# IMSAI_SIO_Emulation.net
KiCad netlist of a schematic drawn in Altium Designer
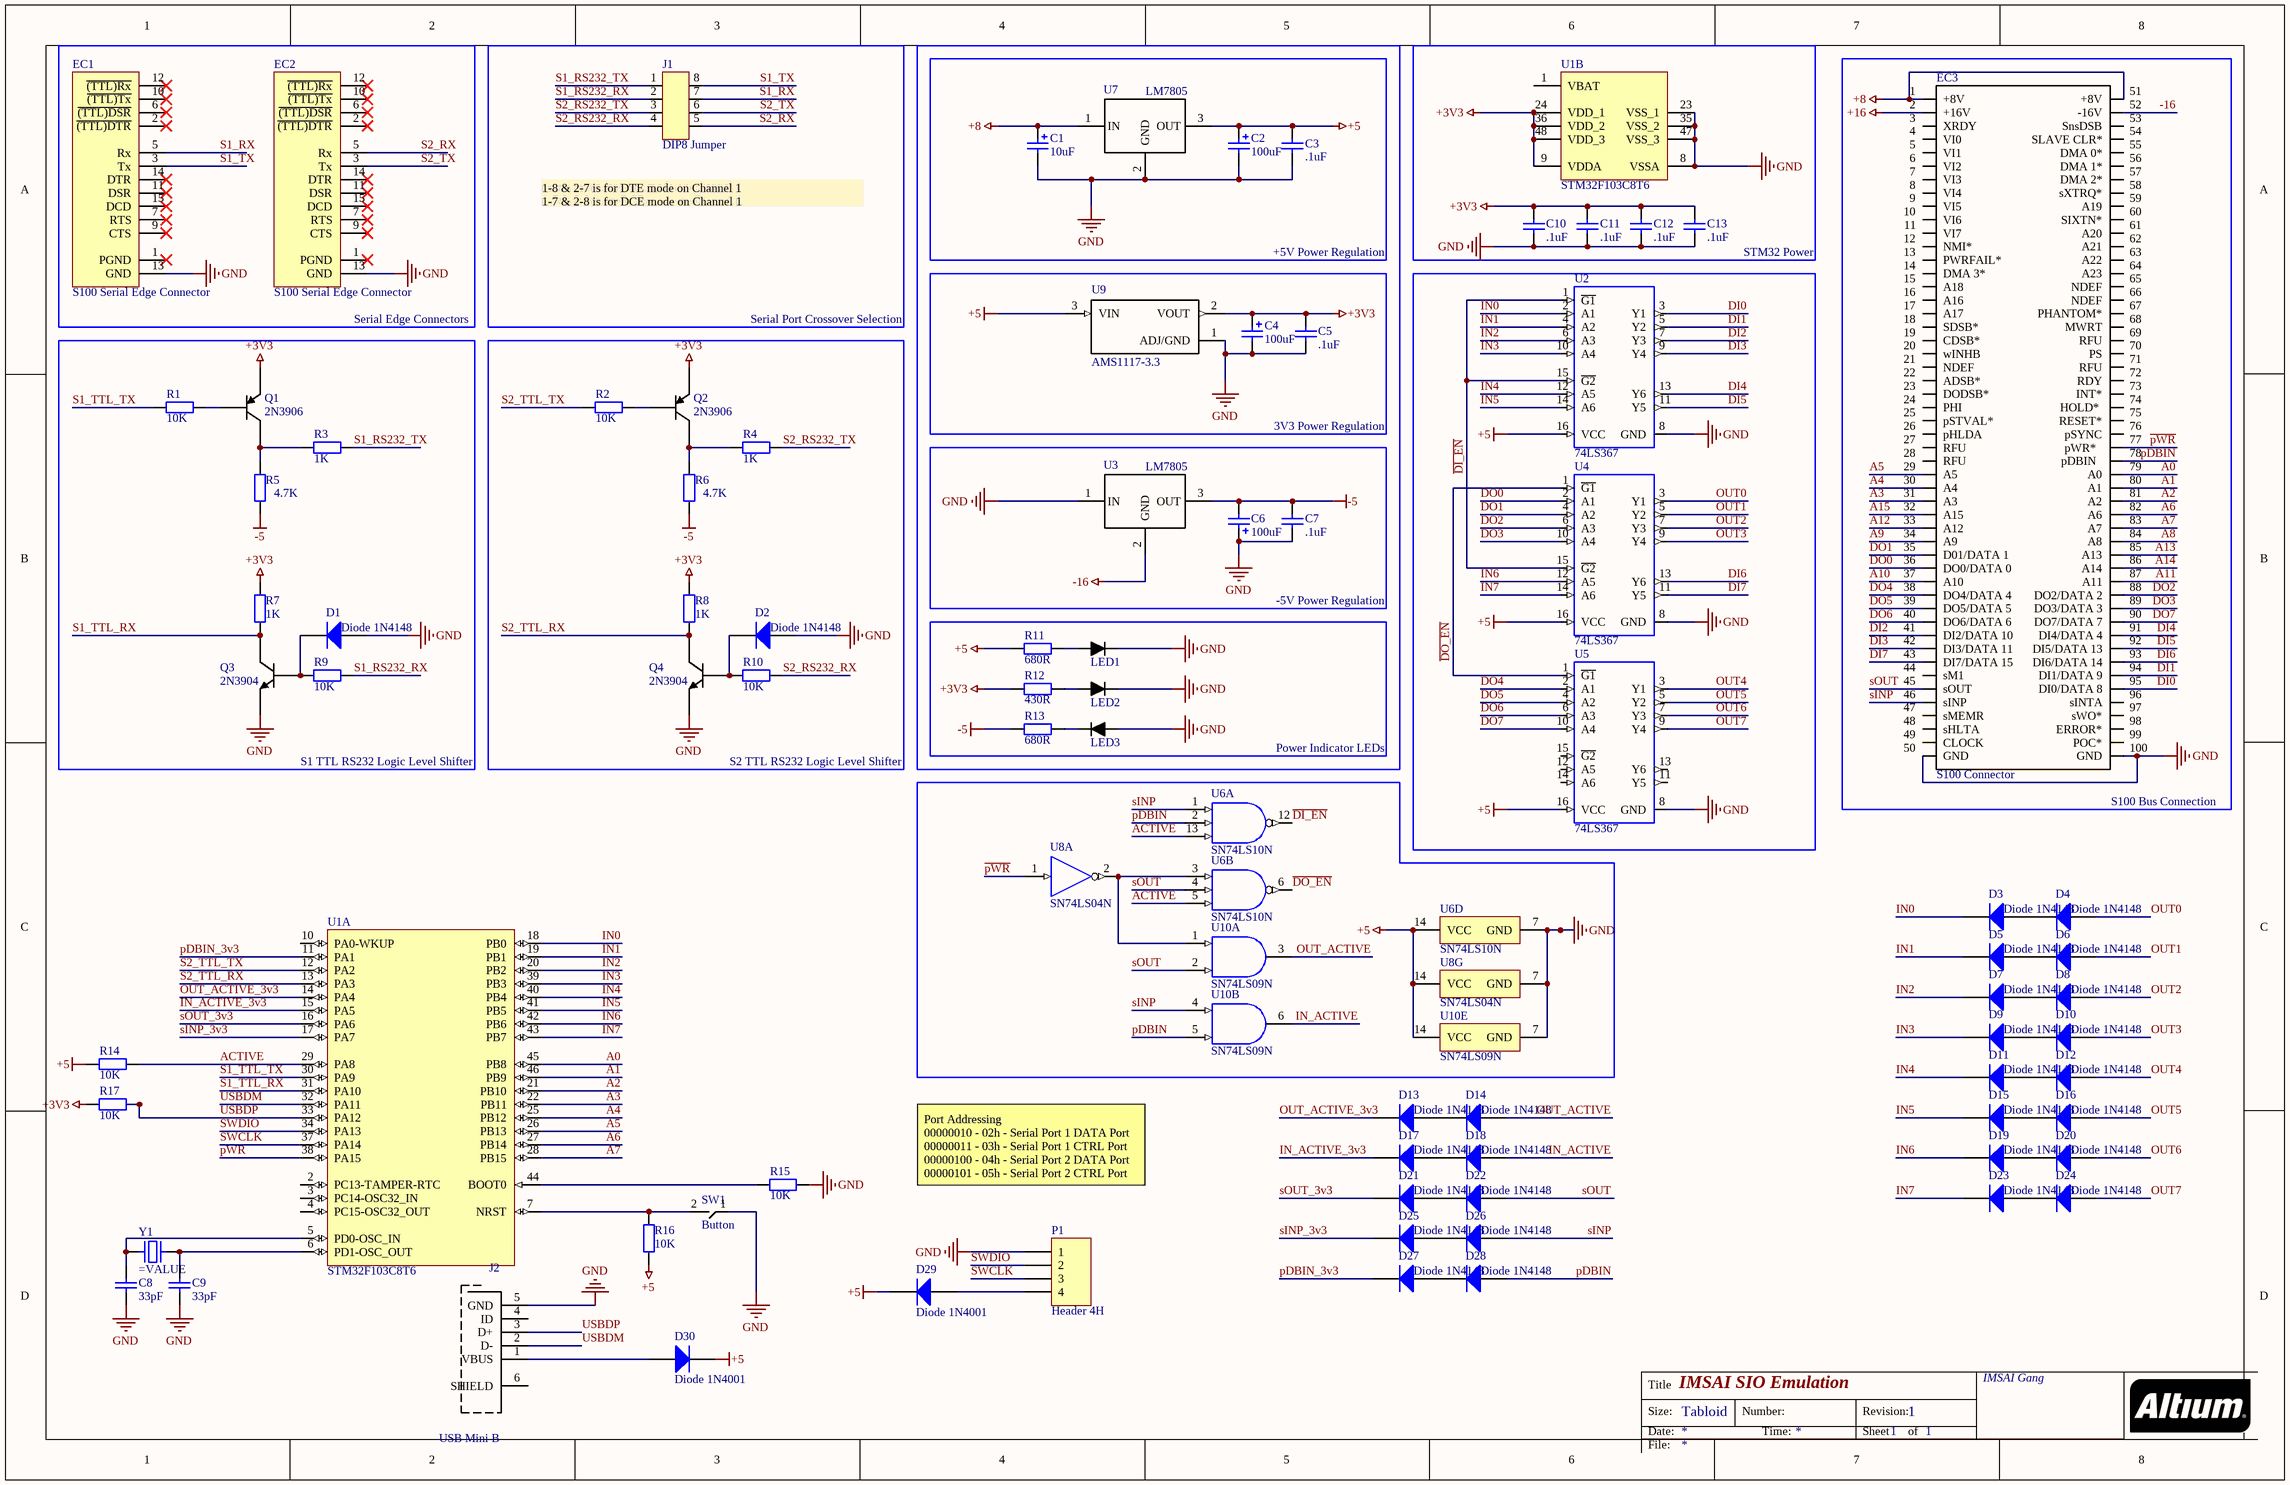
[diagram p0: IMSAI_SIO_Emulation.SchDoc]

(export (version "E")
  (design (tool "Eeschema 10.0.6"))
  (components
    (comp (ref "C1")
      (value "10uF")
      (footprint "Cap THT 2.5-5-11")
      (fields (field (name "Comment") "Capacitor 10uF") (field (name "PUBLISHER") "Altium Limited"))
      (libsource (lib "S100 SCHLIB") (part "Capacitor 10uF"))
    )
    (comp (ref "C2")
      (value "100uF")
      (footprint "CAP THT 2.5-6.5-12")
      (fields (field (name "Comment") "Capacitor 100uF") (field (name "PUBLISHER") "Altium Limited"))
      (libsource (lib "S100 SCHLIB") (part "Capacitor 100uF"))
    )
    (comp (ref "C3")
      (value ".1uF")
      (footprint "CAP THT 2.5x5x5")
      (fields (field (name "Comment") "Capacitor .1uF") (field (name "PUBLISHER") "Altium Limited"))
      (libsource (lib "S100 SCHLIB") (part "Capacitor .1uF"))
    )
    (comp (ref "C4")
      (value "100uF")
      (footprint "CAP THT 2.5-6.5-12")
      (fields (field (name "Comment") "Capacitor 100uF") (field (name "PUBLISHER") "Altium Limited"))
      (libsource (lib "S100 SCHLIB") (part "Capacitor 100uF"))
    )
    (comp (ref "C5")
      (value ".1uF")
      (footprint "CAP THT 2.5x5x5")
      (fields (field (name "Comment") "Capacitor .1uF") (field (name "PUBLISHER") "Altium Limited"))
      (libsource (lib "S100 SCHLIB") (part "Capacitor .1uF"))
    )
    (comp (ref "C6")
      (value "100uF")
      (footprint "CAP THT 2.5-6.5-12")
      (fields (field (name "Comment") "Capacitor 100uF") (field (name "PUBLISHER") "Altium Limited"))
      (libsource (lib "S100 SCHLIB") (part "Capacitor 100uF"))
    )
    (comp (ref "C7")
      (value ".1uF")
      (footprint "CAP THT 2.5x5x5")
      (fields (field (name "Comment") "Capacitor .1uF") (field (name "PUBLISHER") "Altium Limited"))
      (libsource (lib "S100 SCHLIB") (part "Capacitor .1uF"))
    )
    (comp (ref "C8")
      (value "33pF")
      (footprint "Cap THT 2.5-2-4 Ceramic")
      (fields (field (name "Comment") "Capacitor 33pF") (field (name "PUBLISHER") "Altium Limited"))
      (libsource (lib "S100 SCHLIB") (part "Capacitor 33pF"))
    )
    (comp (ref "C9")
      (value "33pF")
      (footprint "Cap THT 2.5-2-4 Ceramic")
      (fields (field (name "Comment") "Capacitor 33pF") (field (name "PUBLISHER") "Altium Limited"))
      (libsource (lib "S100 SCHLIB") (part "Capacitor 33pF"))
    )
    (comp (ref "C10")
      (value ".1uF")
      (footprint "CAP THT 2.5x5x5")
      (fields (field (name "Comment") "Capacitor .1uF") (field (name "PUBLISHER") "Altium Limited"))
      (libsource (lib "S100 SCHLIB") (part "Capacitor .1uF"))
    )
    (comp (ref "C11")
      (value ".1uF")
      (footprint "CAP THT 2.5x5x5")
      (fields (field (name "Comment") "Capacitor .1uF") (field (name "PUBLISHER") "Altium Limited"))
      (libsource (lib "S100 SCHLIB") (part "Capacitor .1uF"))
    )
    (comp (ref "C12")
      (value ".1uF")
      (footprint "CAP THT 2.5x5x5")
      (fields (field (name "Comment") "Capacitor .1uF") (field (name "PUBLISHER") "Altium Limited"))
      (libsource (lib "S100 SCHLIB") (part "Capacitor .1uF"))
    )
    (comp (ref "C13")
      (value ".1uF")
      (footprint "CAP THT 2.5x5x5")
      (fields (field (name "Comment") "Capacitor .1uF") (field (name "PUBLISHER") "Altium Limited"))
      (libsource (lib "S100 SCHLIB") (part "Capacitor .1uF"))
    )
    (comp (ref "D1")
      (value "Diode 1N4148")
      (footprint "DO-35")
      (description "High Conductance Fast Diode")
      (fields (field (name "PUBLISHER") "Altium Limited"))
      (libsource (lib "Miscellaneous Devices") (part "Diode 1N4148"))
    )
    (comp (ref "D2")
      (value "Diode 1N4148")
      (footprint "DO-35")
      (description "High Conductance Fast Diode")
      (fields (field (name "PUBLISHER") "Altium Limited"))
      (libsource (lib "Miscellaneous Devices") (part "Diode 1N4148"))
    )
    (comp (ref "D3")
      (value "Diode 1N4148")
      (footprint "DO-35")
      (description "High Conductance Fast Diode")
      (fields (field (name "PUBLISHER") "Altium Limited"))
      (libsource (lib "Miscellaneous Devices") (part "Diode 1N4148"))
    )
    (comp (ref "D4")
      (value "Diode 1N4148")
      (footprint "DO-35")
      (description "High Conductance Fast Diode")
      (fields (field (name "PUBLISHER") "Altium Limited"))
      (libsource (lib "Miscellaneous Devices") (part "Diode 1N4148"))
    )
    (comp (ref "D5")
      (value "Diode 1N4148")
      (footprint "DO-35")
      (description "High Conductance Fast Diode")
      (fields (field (name "PUBLISHER") "Altium Limited"))
      (libsource (lib "Miscellaneous Devices") (part "Diode 1N4148"))
    )
    (comp (ref "D6")
      (value "Diode 1N4148")
      (footprint "DO-35")
      (description "High Conductance Fast Diode")
      (fields (field (name "PUBLISHER") "Altium Limited"))
      (libsource (lib "Miscellaneous Devices") (part "Diode 1N4148"))
    )
    (comp (ref "D7")
      (value "Diode 1N4148")
      (footprint "DO-35")
      (description "High Conductance Fast Diode")
      (fields (field (name "PUBLISHER") "Altium Limited"))
      (libsource (lib "Miscellaneous Devices") (part "Diode 1N4148"))
    )
    (comp (ref "D8")
      (value "Diode 1N4148")
      (footprint "DO-35")
      (description "High Conductance Fast Diode")
      (fields (field (name "PUBLISHER") "Altium Limited"))
      (libsource (lib "Miscellaneous Devices") (part "Diode 1N4148"))
    )
    (comp (ref "D9")
      (value "Diode 1N4148")
      (footprint "DO-35")
      (description "High Conductance Fast Diode")
      (fields (field (name "PUBLISHER") "Altium Limited"))
      (libsource (lib "Miscellaneous Devices") (part "Diode 1N4148"))
    )
    (comp (ref "D10")
      (value "Diode 1N4148")
      (footprint "DO-35")
      (description "High Conductance Fast Diode")
      (fields (field (name "PUBLISHER") "Altium Limited"))
      (libsource (lib "Miscellaneous Devices") (part "Diode 1N4148"))
    )
    (comp (ref "D11")
      (value "Diode 1N4148")
      (footprint "DO-35")
      (description "High Conductance Fast Diode")
      (fields (field (name "PUBLISHER") "Altium Limited"))
      (libsource (lib "Miscellaneous Devices") (part "Diode 1N4148"))
    )
    (comp (ref "D12")
      (value "Diode 1N4148")
      (footprint "DO-35")
      (description "High Conductance Fast Diode")
      (fields (field (name "PUBLISHER") "Altium Limited"))
      (libsource (lib "Miscellaneous Devices") (part "Diode 1N4148"))
    )
    (comp (ref "D13")
      (value "Diode 1N4148")
      (footprint "DO-35")
      (description "High Conductance Fast Diode")
      (fields (field (name "PUBLISHER") "Altium Limited"))
      (libsource (lib "Miscellaneous Devices") (part "Diode 1N4148"))
    )
    (comp (ref "D14")
      (value "Diode 1N4148")
      (footprint "DO-35")
      (description "High Conductance Fast Diode")
      (fields (field (name "PUBLISHER") "Altium Limited"))
      (libsource (lib "Miscellaneous Devices") (part "Diode 1N4148"))
    )
    (comp (ref "D15")
      (value "Diode 1N4148")
      (footprint "DO-35")
      (description "High Conductance Fast Diode")
      (fields (field (name "PUBLISHER") "Altium Limited"))
      (libsource (lib "Miscellaneous Devices") (part "Diode 1N4148"))
    )
    (comp (ref "D16")
      (value "Diode 1N4148")
      (footprint "DO-35")
      (description "High Conductance Fast Diode")
      (fields (field (name "PUBLISHER") "Altium Limited"))
      (libsource (lib "Miscellaneous Devices") (part "Diode 1N4148"))
    )
    (comp (ref "D17")
      (value "Diode 1N4148")
      (footprint "DO-35")
      (description "High Conductance Fast Diode")
      (fields (field (name "PUBLISHER") "Altium Limited"))
      (libsource (lib "Miscellaneous Devices") (part "Diode 1N4148"))
    )
    (comp (ref "D18")
      (value "Diode 1N4148")
      (footprint "DO-35")
      (description "High Conductance Fast Diode")
      (fields (field (name "PUBLISHER") "Altium Limited"))
      (libsource (lib "Miscellaneous Devices") (part "Diode 1N4148"))
    )
    (comp (ref "D19")
      (value "Diode 1N4148")
      (footprint "DO-35")
      (description "High Conductance Fast Diode")
      (fields (field (name "PUBLISHER") "Altium Limited"))
      (libsource (lib "Miscellaneous Devices") (part "Diode 1N4148"))
    )
    (comp (ref "D20")
      (value "Diode 1N4148")
      (footprint "DO-35")
      (description "High Conductance Fast Diode")
      (fields (field (name "PUBLISHER") "Altium Limited"))
      (libsource (lib "Miscellaneous Devices") (part "Diode 1N4148"))
    )
    (comp (ref "D21")
      (value "Diode 1N4148")
      (footprint "DO-35")
      (description "High Conductance Fast Diode")
      (fields (field (name "PUBLISHER") "Altium Limited"))
      (libsource (lib "Miscellaneous Devices") (part "Diode 1N4148"))
    )
    (comp (ref "D22")
      (value "Diode 1N4148")
      (footprint "DO-35")
      (description "High Conductance Fast Diode")
      (fields (field (name "PUBLISHER") "Altium Limited"))
      (libsource (lib "Miscellaneous Devices") (part "Diode 1N4148"))
    )
    (comp (ref "D23")
      (value "Diode 1N4148")
      (footprint "DO-35")
      (description "High Conductance Fast Diode")
      (fields (field (name "PUBLISHER") "Altium Limited"))
      (libsource (lib "Miscellaneous Devices") (part "Diode 1N4148"))
    )
    (comp (ref "D24")
      (value "Diode 1N4148")
      (footprint "DO-35")
      (description "High Conductance Fast Diode")
      (fields (field (name "PUBLISHER") "Altium Limited"))
      (libsource (lib "Miscellaneous Devices") (part "Diode 1N4148"))
    )
    (comp (ref "D25")
      (value "Diode 1N4148")
      (footprint "DO-35")
      (description "High Conductance Fast Diode")
      (fields (field (name "PUBLISHER") "Altium Limited"))
      (libsource (lib "Miscellaneous Devices") (part "Diode 1N4148"))
    )
    (comp (ref "D26")
      (value "Diode 1N4148")
      (footprint "DO-35")
      (description "High Conductance Fast Diode")
      (fields (field (name "PUBLISHER") "Altium Limited"))
      (libsource (lib "Miscellaneous Devices") (part "Diode 1N4148"))
    )
    (comp (ref "D27")
      (value "Diode 1N4148")
      (footprint "DO-35")
      (description "High Conductance Fast Diode")
      (fields (field (name "PUBLISHER") "Altium Limited"))
      (libsource (lib "Miscellaneous Devices") (part "Diode 1N4148"))
    )
    (comp (ref "D28")
      (value "Diode 1N4148")
      (footprint "DO-35")
      (description "High Conductance Fast Diode")
      (fields (field (name "PUBLISHER") "Altium Limited"))
      (libsource (lib "Miscellaneous Devices") (part "Diode 1N4148"))
    )
    (comp (ref "D29")
      (value "Diode 1N4001")
      (footprint "DO-41")
      (description "1 Amp General Purpose Rectifier")
      (fields (field (name "PUBLISHER") "Altium Limited"))
      (libsource (lib "Miscellaneous Devices") (part "Diode 1N4001"))
    )
    (comp (ref "D30")
      (value "Diode 1N4001")
      (footprint "DO-41")
      (description "1 Amp General Purpose Rectifier")
      (fields (field (name "PUBLISHER") "Altium Limited"))
      (libsource (lib "Miscellaneous Devices") (part "Diode 1N4001"))
    )
    (comp (ref "EC1")
      (value "S100 Serial Edge Connector")
      (footprint "E26 Edge Connector")
      (libsource (lib "S100 SCHLIB") (part "S100 Serial Edge Connector"))
    )
    (comp (ref "EC2")
      (value "S100 Serial Edge Connector")
      (footprint "E26 Edge Connector")
      (libsource (lib "S100 SCHLIB") (part "S100 Serial Edge Connector"))
    )
    (comp (ref "EC3")
      (value "S100 Connector")
      (footprint "S100")
      (libsource (lib "S100 SCHLIB") (part "S100 Connector"))
    )
    (comp (ref "J1")
      (value "DIP8 Jumper")
      (footprint "DIP8")
      (libsource (lib "S100 SCHLIB") (part "DIP8 Jumper"))
    )
    (comp (ref "J2")
      (value "USB Mini B")
      (footprint "USB Mini B")
      (description "MINI USB A - 5POS Horizontal through hole")
      (fields (field (name "MF") "Wurth Electronics") (field (name "MP") "651005136521"))
      (libsource (lib "S100 SCHLIB") (part "USB Mini B"))
    )
    (comp (ref "LED1")
      (value "Generic LED 5mm")
      (footprint "LED 5mm THT")
      (libsource (lib "S100 SCHLIB") (part "Generic LED 5mm"))
    )
    (comp (ref "LED2")
      (value "Generic LED 5mm")
      (footprint "LED 5mm THT")
      (libsource (lib "S100 SCHLIB") (part "Generic LED 5mm"))
    )
    (comp (ref "LED3")
      (value "Generic LED 5mm")
      (footprint "LED 5mm THT")
      (libsource (lib "S100 SCHLIB") (part "Generic LED 5mm"))
    )
    (comp (ref "P1")
      (value "Header 4H")
      (footprint "HDR1X4H")
      (description "Header, 4-Pin, Right Angle")
      (fields (field (name "PUBLISHER") "Altium Limited"))
      (libsource (lib "Miscellaneous Connectors") (part "Header 4H"))
    )
    (comp (ref "Q1")
      (value "2N3906")
      (footprint "TO-92A")
      (description "2N3906 GP PNP")
      (fields (field (name "PUBLISHER") "Altium Limited"))
      (libsource (lib "S100 SCHLIB") (part "2N3906"))
    )
    (comp (ref "Q2")
      (value "2N3906")
      (footprint "TO-92A")
      (description "2N3906 GP PNP")
      (fields (field (name "PUBLISHER") "Altium Limited"))
      (libsource (lib "S100 SCHLIB") (part "2N3906"))
    )
    (comp (ref "Q3")
      (value "2N3904")
      (footprint "TO-92A")
      (description "NPN General Purpose Amplifier")
      (fields (field (name "PUBLISHER") "Altium Limited"))
      (libsource (lib "S100 SCHLIB") (part "2N3904"))
    )
    (comp (ref "Q4")
      (value "2N3904")
      (footprint "TO-92A")
      (description "NPN General Purpose Amplifier")
      (fields (field (name "PUBLISHER") "Altium Limited"))
      (libsource (lib "S100 SCHLIB") (part "2N3904"))
    )
    (comp (ref "R1")
      (value "Res2")
      (footprint "AXIAL-0.4")
      (description "Resistor")
      (fields (field (name "ALTIUM_UNNAMED_1") "10K") (field (name "PUBLISHER") "Altium Limited"))
      (libsource (lib "Miscellaneous Devices") (part "Res2"))
    )
    (comp (ref "R2")
      (value "Res2")
      (footprint "AXIAL-0.4")
      (description "Resistor")
      (fields (field (name "ALTIUM_UNNAMED_1") "10K") (field (name "PUBLISHER") "Altium Limited"))
      (libsource (lib "Miscellaneous Devices") (part "Res2"))
    )
    (comp (ref "R3")
      (value "Res2")
      (footprint "AXIAL-0.4")
      (description "Resistor")
      (fields (field (name "ALTIUM_UNNAMED_1") "1K") (field (name "PUBLISHER") "Altium Limited"))
      (libsource (lib "Miscellaneous Devices") (part "Res2"))
    )
    (comp (ref "R4")
      (value "Res2")
      (footprint "AXIAL-0.4")
      (description "Resistor")
      (fields (field (name "ALTIUM_UNNAMED_1") "1K") (field (name "PUBLISHER") "Altium Limited"))
      (libsource (lib "Miscellaneous Devices") (part "Res2"))
    )
    (comp (ref "R5")
      (value "Res2")
      (footprint "AXIAL-0.4")
      (description "Resistor")
      (fields (field (name "ALTIUM_UNNAMED_1") "4.7K") (field (name "PUBLISHER") "Altium Limited"))
      (libsource (lib "") (part "Res2_2"))
    )
    (comp (ref "R6")
      (value "Res2")
      (footprint "AXIAL-0.4")
      (description "Resistor")
      (fields (field (name "ALTIUM_UNNAMED_1") "4.7K") (field (name "PUBLISHER") "Altium Limited"))
      (libsource (lib "") (part "Res2_2"))
    )
    (comp (ref "R7")
      (value "Res2")
      (footprint "AXIAL-0.4")
      (description "Resistor")
      (fields (field (name "ALTIUM_UNNAMED_1") "1K") (field (name "PUBLISHER") "Altium Limited"))
      (libsource (lib "") (part "Res2_1"))
    )
    (comp (ref "R8")
      (value "Res2")
      (footprint "AXIAL-0.4")
      (description "Resistor")
      (fields (field (name "ALTIUM_UNNAMED_1") "1K") (field (name "PUBLISHER") "Altium Limited"))
      (libsource (lib "") (part "Res2_1"))
    )
    (comp (ref "R9")
      (value "Res2")
      (footprint "AXIAL-0.4")
      (description "Resistor")
      (fields (field (name "ALTIUM_UNNAMED_1") "10K") (field (name "PUBLISHER") "Altium Limited"))
      (libsource (lib "Miscellaneous Devices") (part "Res2"))
    )
    (comp (ref "R10")
      (value "Res2")
      (footprint "AXIAL-0.4")
      (description "Resistor")
      (fields (field (name "ALTIUM_UNNAMED_1") "10K") (field (name "PUBLISHER") "Altium Limited"))
      (libsource (lib "Miscellaneous Devices") (part "Res2"))
    )
    (comp (ref "R11")
      (value "Res2")
      (footprint "AXIAL-0.4")
      (description "Resistor")
      (fields (field (name "ALTIUM_UNNAMED_1") "680R") (field (name "PUBLISHER") "Altium Limited"))
      (libsource (lib "Miscellaneous Devices") (part "Res2"))
    )
    (comp (ref "R12")
      (value "Res2")
      (footprint "AXIAL-0.4")
      (description "Resistor")
      (fields (field (name "ALTIUM_UNNAMED_1") "430R") (field (name "PUBLISHER") "Altium Limited"))
      (libsource (lib "Miscellaneous Devices") (part "Res2"))
    )
    (comp (ref "R13")
      (value "Res2")
      (footprint "AXIAL-0.4")
      (description "Resistor")
      (fields (field (name "ALTIUM_UNNAMED_1") "680R") (field (name "PUBLISHER") "Altium Limited"))
      (libsource (lib "Miscellaneous Devices") (part "Res2"))
    )
    (comp (ref "R14")
      (value "Res2")
      (footprint "AXIAL-0.4")
      (description "Resistor")
      (fields (field (name "ALTIUM_UNNAMED_1") "10K") (field (name "PUBLISHER") "Altium Limited"))
      (libsource (lib "Miscellaneous Devices") (part "Res2"))
    )
    (comp (ref "R15")
      (value "Res2")
      (footprint "AXIAL-0.4")
      (description "Resistor")
      (fields (field (name "ALTIUM_UNNAMED_1") "10K") (field (name "PUBLISHER") "Altium Limited"))
      (libsource (lib "Miscellaneous Devices") (part "Res2"))
    )
    (comp (ref "R16")
      (value "Res2")
      (footprint "AXIAL-0.4")
      (description "Resistor")
      (fields (field (name "ALTIUM_UNNAMED_1") "10K") (field (name "PUBLISHER") "Altium Limited"))
      (libsource (lib "") (part "Res2_1"))
    )
    (comp (ref "R17")
      (value "Res2")
      (footprint "AXIAL-0.4")
      (description "Resistor")
      (fields (field (name "ALTIUM_UNNAMED_1") "10K") (field (name "PUBLISHER") "Altium Limited"))
      (libsource (lib "Miscellaneous Devices") (part "Res2"))
    )
    (comp (ref "SW1")
      (value "Button")
      (footprint "SMD_PUSHBUTTON_LCSC")
      (description "LCSC Push button SMD")
      (libsource (lib "S100 SCHLIB") (part "Button"))
    )
    (comp (ref "U1")
      (value "STM32F103C8T6")
      (footprint "STM-LQFP48_L")
      (libsource (lib "STMicroelectronics STM32 F1") (part "STM32F103C8T6"))
    )
    (comp (ref "U2") (value "74LS367") (footprint "DIP16") (libsource (lib "S100 SCHLIB") (part "74LS367")))
    (comp (ref "U3")
      (value "LM7805")
      (footprint "TO220")
      (description "LM7805 Linear Voltage Regulator")
      (libsource (lib "S100 SCHLIB") (part "LM7805"))
    )
    (comp (ref "U4") (value "74LS367") (footprint "DIP16") (libsource (lib "S100 SCHLIB") (part "74LS367")))
    (comp (ref "U5") (value "74LS367") (footprint "DIP16") (libsource (lib "S100 SCHLIB") (part "74LS367")))
    (comp (ref "U6")
      (value "SN74LS10N")
      (footprint "N0014A")
      (description "Triple 3-input positive-NAND gates, N0014A, TUBE")
      (fields
        (field (name "GENERIC PART NUMBER") "SN74LS10")
        (field (name "MANUFACTURER") "Texas Instruments")
      )
      (libsource (lib "TI_Logic_Gate") (part "SN74LS10N"))
    )
    (comp (ref "U7")
      (value "LM7805")
      (footprint "TO220")
      (description "LM7805 Linear Voltage Regulator")
      (libsource (lib "S100 SCHLIB") (part "LM7805"))
    )
    (comp (ref "U8")
      (value "SN74LS04N")
      (footprint "N0014A")
      (description "Hex inverters, N0014A, TUBE")
      (fields
        (field (name "GENERIC PART NUMBER") "SN74LS04")
        (field (name "MANUFACTURER") "Texas Instruments")
      )
      (libsource (lib "TI_Logic_Buffer,Driver,Transceiver") (part "SN74LS04N"))
    )
    (comp (ref "U9")
      (value "AMS1117-3.3")
      (footprint "TO220")
      (description "1-Amp 3.3-Volt Low Drop Out Voltage Regulatator")
      (fields (field (name "MF") "Advanced Monolithic Systems"))
      (libsource (lib "S100 SCHLIB") (part "AMS1117-3.3"))
    )
    (comp (ref "U10")
      (value "SN74LS09N")
      (footprint "N0014A")
      (description "Quad 2-input positive-AND gates with open collector outputs, N0014A, TUBE")
      (fields
        (field (name "GENERIC PART NUMBER") "SN74LS09")
        (field (name "MANUFACTURER") "Texas Instruments")
      )
      (libsource (lib "TI_Logic_Gate") (part "SN74LS09N"))
    )
    (comp (ref "Y1")
      (value "~")
      (footprint "ABRACON ABLS")
      (description "SMT Crystal")
      (libsource (lib "S100 SCHLIB") (part "Abracon Crystal ABLS"))
    )
  )
  (nets
    (net (code "1") (name "+3V3") (class "Default")
      (node (ref "C10") (pin "2") (pinfunction "2_2") (pintype "passive"))
      (node (ref "C11") (pin "2") (pinfunction "2_2") (pintype "passive"))
      (node (ref "C12") (pin "2") (pinfunction "2_2") (pintype "passive"))
      (node (ref "C13") (pin "2") (pinfunction "2_2") (pintype "passive"))
      (node (ref "C4") (pin "1") (pinfunction "1_1") (pintype "passive"))
      (node (ref "C5") (pin "2") (pinfunction "2_2") (pintype "passive"))
      (node (ref "Q1") (pin "1") (pinfunction "E_1") (pintype "passive"))
      (node (ref "Q2") (pin "1") (pinfunction "E_1") (pintype "passive"))
      (node (ref "R12") (pin "2") (pinfunction "2_2") (pintype "passive"))
      (node (ref "R17") (pin "2") (pinfunction "2_2") (pintype "passive"))
      (node (ref "R7") (pin "1") (pinfunction "1_1") (pintype "passive"))
      (node (ref "R8") (pin "1") (pinfunction "1_1") (pintype "passive"))
      (node (ref "U1") (pin "24") (pinfunction "VDD_1_24") (pintype "power_in"))
      (node (ref "U1") (pin "36") (pinfunction "VDD_2_36") (pintype "power_in"))
      (node (ref "U1") (pin "48") (pinfunction "VDD_3_48") (pintype "power_in"))
      (node (ref "U1") (pin "9") (pinfunction "VDDA_9") (pintype "power_in"))
      (node (ref "U9") (pin "2") (pinfunction "VOUT_2") (pintype "output"))
    )
    (net (code "2") (name "+5") (class "Default")
      (node (ref "C2") (pin "1") (pinfunction "1_1") (pintype "passive"))
      (node (ref "C3") (pin "2") (pinfunction "2_2") (pintype "passive"))
      (node (ref "D29") (pin "2") (pinfunction "K_2") (pintype "passive"))
      (node (ref "D30") (pin "2") (pinfunction "K_2") (pintype "passive"))
      (node (ref "R11") (pin "2") (pinfunction "2_2") (pintype "passive"))
      (node (ref "R14") (pin "2") (pinfunction "2_2") (pintype "passive"))
      (node (ref "R16") (pin "2") (pinfunction "2_2") (pintype "passive"))
      (node (ref "U10") (pin "14") (pinfunction "VCC_14") (pintype "power_in"))
      (node (ref "U2") (pin "16") (pinfunction "VCC_16") (pintype "input"))
      (node (ref "U4") (pin "16") (pinfunction "VCC_16") (pintype "input"))
      (node (ref "U5") (pin "16") (pinfunction "VCC_16") (pintype "input"))
      (node (ref "U6") (pin "14") (pinfunction "VCC_14") (pintype "power_in"))
      (node (ref "U7") (pin "3") (pinfunction "OUT_3") (pintype "passive"))
      (node (ref "U8") (pin "14") (pinfunction "VCC_14") (pintype "power_in"))
      (node (ref "U9") (pin "3") (pinfunction "VIN_3") (pintype "input"))
    )
    (net (code "3") (name "+8") (class "Default")
      (node (ref "C1") (pin "1") (pinfunction "1_1") (pintype "passive"))
      (node (ref "EC3") (pin "1") (pinfunction "+8V_1") (pintype "passive"))
      (node (ref "EC3") (pin "51") (pinfunction "+8V_51") (pintype "passive"))
      (node (ref "U7") (pin "1") (pinfunction "IN_1") (pintype "passive"))
    )
    (net (code "4") (name "+16") (class "Default")
      (node (ref "EC3") (pin "2") (pinfunction "+16V_2") (pintype "passive"))
    )
    (net (code "5") (name "-5") (class "Default")
      (node (ref "C6") (pin "2") (pinfunction "2_2") (pintype "passive"))
      (node (ref "C7") (pin "1") (pinfunction "1_1") (pintype "passive"))
      (node (ref "R13") (pin "2") (pinfunction "2_2") (pintype "passive"))
      (node (ref "R5") (pin "1") (pinfunction "1_1") (pintype "passive"))
      (node (ref "R6") (pin "1") (pinfunction "1_1") (pintype "passive"))
      (node (ref "U3") (pin "3") (pinfunction "OUT_3") (pintype "passive"))
    )
    (net (code "6") (name "-16") (class "Default")
      (node (ref "EC3") (pin "52") (pinfunction "-16V_52") (pintype "passive"))
      (node (ref "U3") (pin "2") (pinfunction "GND_2") (pintype "passive"))
    )
    (net (code "7") (name "/A0") (class "Default")
      (node (ref "EC3") (pin "79") (pinfunction "A0_79") (pintype "passive"))
      (node (ref "U1") (pin "45") (pinfunction "PB8_45") (pintype "bidirectional"))
    )
    (net (code "8") (name "/A1") (class "Default")
      (node (ref "EC3") (pin "80") (pinfunction "A1_80") (pintype "passive"))
      (node (ref "U1") (pin "46") (pinfunction "PB9_46") (pintype "bidirectional"))
    )
    (net (code "9") (name "/A2") (class "Default")
      (node (ref "EC3") (pin "81") (pinfunction "A2_81") (pintype "passive"))
      (node (ref "U1") (pin "21") (pinfunction "PB10_21") (pintype "bidirectional"))
    )
    (net (code "10") (name "/A3") (class "Default")
      (node (ref "EC3") (pin "31") (pinfunction "A3_31") (pintype "passive"))
      (node (ref "U1") (pin "22") (pinfunction "PB11_22") (pintype "bidirectional"))
    )
    (net (code "11") (name "/A4") (class "Default")
      (node (ref "EC3") (pin "30") (pinfunction "A4_30") (pintype "passive"))
      (node (ref "U1") (pin "25") (pinfunction "PB12_25") (pintype "bidirectional"))
    )
    (net (code "12") (name "/A5") (class "Default")
      (node (ref "EC3") (pin "29") (pinfunction "A5_29") (pintype "passive"))
      (node (ref "U1") (pin "26") (pinfunction "PB13_26") (pintype "bidirectional"))
    )
    (net (code "13") (name "/A6") (class "Default")
      (node (ref "EC3") (pin "82") (pinfunction "A6_82") (pintype "passive"))
      (node (ref "U1") (pin "27") (pinfunction "PB14_27") (pintype "bidirectional"))
    )
    (net (code "14") (name "/A7") (class "Default")
      (node (ref "EC3") (pin "83") (pinfunction "A7_83") (pintype "passive"))
      (node (ref "U1") (pin "28") (pinfunction "PB15_28") (pintype "bidirectional"))
    )
    (net (code "15") (name "/A8") (class "Default")
      (node (ref "EC3") (pin "84") (pinfunction "A8_84") (pintype "passive"))
    )
    (net (code "16") (name "/A9") (class "Default")
      (node (ref "EC3") (pin "34") (pinfunction "A9_34") (pintype "passive"))
    )
    (net (code "17") (name "/A10") (class "Default")
      (node (ref "EC3") (pin "37") (pinfunction "A10_37") (pintype "passive"))
    )
    (net (code "18") (name "/A11") (class "Default")
      (node (ref "EC3") (pin "87") (pinfunction "A11_87") (pintype "passive"))
    )
    (net (code "19") (name "/A12") (class "Default")
      (node (ref "EC3") (pin "33") (pinfunction "A12_33") (pintype "passive"))
    )
    (net (code "20") (name "/A13") (class "Default")
      (node (ref "EC3") (pin "85") (pinfunction "A13_85") (pintype "passive"))
    )
    (net (code "21") (name "/A14") (class "Default")
      (node (ref "EC3") (pin "86") (pinfunction "A14_86") (pintype "passive"))
    )
    (net (code "22") (name "/A15") (class "Default")
      (node (ref "EC3") (pin "32") (pinfunction "A15_32") (pintype "passive"))
    )
    (net (code "23") (name "/ACTIVE") (class "Default")
      (node (ref "R14") (pin "1") (pinfunction "1_1") (pintype "passive"))
      (node (ref "U1") (pin "29") (pinfunction "PA8_29") (pintype "bidirectional"))
      (node (ref "U6") (pin "13") (pinfunction "1C_13") (pintype "input"))
      (node (ref "U6") (pin "5") (pinfunction "2C_5") (pintype "input"))
    )
    (net (code "24") (name "/DI0") (class "Default")
      (node (ref "EC3") (pin "95") (pinfunction "DI0/DATA_8_95") (pintype "passive"))
      (node (ref "U2") (pin "3") (pinfunction "Y1_3") (pintype "output"))
    )
    (net (code "25") (name "/DI1") (class "Default")
      (node (ref "EC3") (pin "94") (pinfunction "DI1/DATA_9_94") (pintype "passive"))
      (node (ref "U2") (pin "5") (pinfunction "Y2_5") (pintype "output"))
    )
    (net (code "26") (name "/DI2") (class "Default")
      (node (ref "EC3") (pin "41") (pinfunction "DI2/DATA_10_41") (pintype "passive"))
      (node (ref "U2") (pin "7") (pinfunction "Y3_7") (pintype "output"))
    )
    (net (code "27") (name "/DI3") (class "Default")
      (node (ref "EC3") (pin "42") (pinfunction "DI3/DATA_11_42") (pintype "passive"))
      (node (ref "U2") (pin "9") (pinfunction "Y4_9") (pintype "output"))
    )
    (net (code "28") (name "/DI4") (class "Default")
      (node (ref "EC3") (pin "91") (pinfunction "DI4/DATA_4_91") (pintype "passive"))
      (node (ref "U2") (pin "13") (pinfunction "Y6_13") (pintype "output"))
    )
    (net (code "29") (name "/DI5") (class "Default")
      (node (ref "EC3") (pin "92") (pinfunction "DI5/DATA_13_92") (pintype "passive"))
      (node (ref "U2") (pin "11") (pinfunction "Y5_11") (pintype "output"))
    )
    (net (code "30") (name "/DI6") (class "Default")
      (node (ref "EC3") (pin "93") (pinfunction "DI6/DATA_14_93") (pintype "passive"))
      (node (ref "U4") (pin "13") (pinfunction "Y6_13") (pintype "output"))
    )
    (net (code "31") (name "/DI7") (class "Default")
      (node (ref "EC3") (pin "43") (pinfunction "DI7/DATA_15_43") (pintype "passive"))
      (node (ref "U4") (pin "11") (pinfunction "Y5_11") (pintype "output"))
    )
    (net (code "32") (name "/DI_EN") (class "Default")
      (node (ref "U2") (pin "1") (pinfunction "G1_1") (pintype "input"))
      (node (ref "U2") (pin "15") (pinfunction "G2_15") (pintype "input"))
      (node (ref "U4") (pin "15") (pinfunction "G2_15") (pintype "input"))
      (node (ref "U6") (pin "12") (pinfunction "1Y_12") (pintype "output"))
    )
    (net (code "33") (name "/DO0") (class "Default")
      (node (ref "EC3") (pin "36") (pinfunction "DO0/DATA_0_36") (pintype "passive"))
      (node (ref "U4") (pin "2") (pinfunction "A1_2") (pintype "input"))
    )
    (net (code "34") (name "/DO1") (class "Default")
      (node (ref "EC3") (pin "35") (pinfunction "D01/DATA_1_35") (pintype "passive"))
      (node (ref "U4") (pin "4") (pinfunction "A2_4") (pintype "input"))
    )
    (net (code "35") (name "/DO2") (class "Default")
      (node (ref "EC3") (pin "88") (pinfunction "DO2/DATA_2_88") (pintype "passive"))
      (node (ref "U4") (pin "6") (pinfunction "A3_6") (pintype "input"))
    )
    (net (code "36") (name "/DO3") (class "Default")
      (node (ref "EC3") (pin "89") (pinfunction "DO3/DATA_3_89") (pintype "passive"))
      (node (ref "U4") (pin "10") (pinfunction "A4_10") (pintype "input"))
    )
    (net (code "37") (name "/DO4") (class "Default")
      (node (ref "EC3") (pin "38") (pinfunction "DO4/DATA_4_38") (pintype "passive"))
      (node (ref "U5") (pin "2") (pinfunction "A1_2") (pintype "input"))
    )
    (net (code "38") (name "/DO5") (class "Default")
      (node (ref "EC3") (pin "39") (pinfunction "DO5/DATA_5_39") (pintype "passive"))
      (node (ref "U5") (pin "4") (pinfunction "A2_4") (pintype "input"))
    )
    (net (code "39") (name "/DO6") (class "Default")
      (node (ref "EC3") (pin "40") (pinfunction "DO6/DATA_6_40") (pintype "passive"))
      (node (ref "U5") (pin "6") (pinfunction "A3_6") (pintype "input"))
    )
    (net (code "40") (name "/DO7") (class "Default")
      (node (ref "EC3") (pin "90") (pinfunction "DO7/DATA_7_90") (pintype "passive"))
      (node (ref "U5") (pin "10") (pinfunction "A4_10") (pintype "input"))
    )
    (net (code "41") (name "/DO_EN") (class "Default")
      (node (ref "U4") (pin "1") (pinfunction "G1_1") (pintype "input"))
      (node (ref "U5") (pin "1") (pinfunction "G1_1") (pintype "input"))
      (node (ref "U6") (pin "6") (pinfunction "2Y_6") (pintype "output"))
    )
    (net (code "42") (name "/IN0") (class "Default")
      (node (ref "D3") (pin "2") (pinfunction "K_2") (pintype "passive"))
      (node (ref "U1") (pin "18") (pinfunction "PB0_18") (pintype "bidirectional"))
      (node (ref "U2") (pin "2") (pinfunction "A1_2") (pintype "input"))
    )
    (net (code "43") (name "/IN1") (class "Default")
      (node (ref "D5") (pin "2") (pinfunction "K_2") (pintype "passive"))
      (node (ref "U1") (pin "19") (pinfunction "PB1_19") (pintype "bidirectional"))
      (node (ref "U2") (pin "4") (pinfunction "A2_4") (pintype "input"))
    )
    (net (code "44") (name "/IN2") (class "Default")
      (node (ref "D7") (pin "2") (pinfunction "K_2") (pintype "passive"))
      (node (ref "U1") (pin "20") (pinfunction "PB2_20") (pintype "bidirectional"))
      (node (ref "U2") (pin "6") (pinfunction "A3_6") (pintype "input"))
    )
    (net (code "45") (name "/IN3") (class "Default")
      (node (ref "D9") (pin "2") (pinfunction "K_2") (pintype "passive"))
      (node (ref "U1") (pin "39") (pinfunction "PB3_39") (pintype "bidirectional"))
      (node (ref "U2") (pin "10") (pinfunction "A4_10") (pintype "input"))
    )
    (net (code "46") (name "/IN4") (class "Default")
      (node (ref "D11") (pin "2") (pinfunction "K_2") (pintype "passive"))
      (node (ref "U1") (pin "40") (pinfunction "PB4_40") (pintype "bidirectional"))
      (node (ref "U2") (pin "12") (pinfunction "A5_12") (pintype "input"))
    )
    (net (code "47") (name "/IN5") (class "Default")
      (node (ref "D15") (pin "2") (pinfunction "K_2") (pintype "passive"))
      (node (ref "U1") (pin "41") (pinfunction "PB5_41") (pintype "bidirectional"))
      (node (ref "U2") (pin "14") (pinfunction "A6_14") (pintype "input"))
    )
    (net (code "48") (name "/IN6") (class "Default")
      (node (ref "D19") (pin "2") (pinfunction "K_2") (pintype "passive"))
      (node (ref "U1") (pin "42") (pinfunction "PB6_42") (pintype "bidirectional"))
      (node (ref "U4") (pin "12") (pinfunction "A5_12") (pintype "input"))
    )
    (net (code "49") (name "/IN7") (class "Default")
      (node (ref "D23") (pin "2") (pinfunction "K_2") (pintype "passive"))
      (node (ref "U1") (pin "43") (pinfunction "PB7_43") (pintype "bidirectional"))
      (node (ref "U4") (pin "14") (pinfunction "A6_14") (pintype "input"))
    )
    (net (code "50") (name "/IN_ACTIVE") (class "Default")
      (node (ref "D18") (pin "1") (pinfunction "A_1") (pintype "passive"))
      (node (ref "U10") (pin "6") (pinfunction "2Y_6") (pintype "open_collector"))
    )
    (net (code "51") (name "/IN_ACTIVE_3v3") (class "Default")
      (node (ref "D17") (pin "2") (pinfunction "K_2") (pintype "passive"))
      (node (ref "U1") (pin "15") (pinfunction "PA5_15") (pintype "bidirectional"))
    )
    (net (code "52") (name "/OUT0") (class "Default")
      (node (ref "D4") (pin "1") (pinfunction "A_1") (pintype "passive"))
      (node (ref "U4") (pin "3") (pinfunction "Y1_3") (pintype "output"))
    )
    (net (code "53") (name "/OUT1") (class "Default")
      (node (ref "D6") (pin "1") (pinfunction "A_1") (pintype "passive"))
      (node (ref "U4") (pin "5") (pinfunction "Y2_5") (pintype "output"))
    )
    (net (code "54") (name "/OUT2") (class "Default")
      (node (ref "D8") (pin "1") (pinfunction "A_1") (pintype "passive"))
      (node (ref "U4") (pin "7") (pinfunction "Y3_7") (pintype "output"))
    )
    (net (code "55") (name "/OUT3") (class "Default")
      (node (ref "D10") (pin "1") (pinfunction "A_1") (pintype "passive"))
      (node (ref "U4") (pin "9") (pinfunction "Y4_9") (pintype "output"))
    )
    (net (code "56") (name "/OUT4") (class "Default")
      (node (ref "D12") (pin "1") (pinfunction "A_1") (pintype "passive"))
      (node (ref "U5") (pin "3") (pinfunction "Y1_3") (pintype "output"))
    )
    (net (code "57") (name "/OUT5") (class "Default")
      (node (ref "D16") (pin "1") (pinfunction "A_1") (pintype "passive"))
      (node (ref "U5") (pin "5") (pinfunction "Y2_5") (pintype "output"))
    )
    (net (code "58") (name "/OUT6") (class "Default")
      (node (ref "D20") (pin "1") (pinfunction "A_1") (pintype "passive"))
      (node (ref "U5") (pin "7") (pinfunction "Y3_7") (pintype "output"))
    )
    (net (code "59") (name "/OUT7") (class "Default")
      (node (ref "D24") (pin "1") (pinfunction "A_1") (pintype "passive"))
      (node (ref "U5") (pin "9") (pinfunction "Y4_9") (pintype "output"))
    )
    (net (code "60") (name "/OUT_ACTIVE") (class "Default")
      (node (ref "D14") (pin "1") (pinfunction "A_1") (pintype "passive"))
      (node (ref "U10") (pin "3") (pinfunction "1Y_3") (pintype "open_collector"))
    )
    (net (code "61") (name "/OUT_ACTIVE_3v3") (class "Default")
      (node (ref "D13") (pin "2") (pinfunction "K_2") (pintype "passive"))
      (node (ref "U1") (pin "14") (pinfunction "PA4_14") (pintype "bidirectional"))
    )
    (net (code "62") (name "/S1_RS232_RX") (class "Default")
      (node (ref "J1") (pin "2") (pintype "passive"))
      (node (ref "R9") (pin "1") (pinfunction "1_1") (pintype "passive"))
    )
    (net (code "63") (name "/S1_RS232_TX") (class "Default")
      (node (ref "J1") (pin "1") (pintype "passive"))
      (node (ref "R3") (pin "1") (pinfunction "1_1") (pintype "passive"))
    )
    (net (code "64") (name "/S1_RX") (class "Default")
      (node (ref "EC1") (pin "5") (pinfunction "Rx_5") (pintype "passive"))
      (node (ref "J1") (pin "7") (pintype "passive"))
    )
    (net (code "65") (name "/S1_TTL_RX") (class "Default")
      (node (ref "Q3") (pin "3") (pinfunction "C_3") (pintype "passive"))
      (node (ref "R7") (pin "2") (pinfunction "2_2") (pintype "passive"))
      (node (ref "U1") (pin "31") (pinfunction "PA10_31") (pintype "bidirectional"))
    )
    (net (code "66") (name "/S1_TTL_TX") (class "Default")
      (node (ref "R1") (pin "2") (pinfunction "2_2") (pintype "passive"))
      (node (ref "U1") (pin "30") (pinfunction "PA9_30") (pintype "bidirectional"))
    )
    (net (code "67") (name "/S1_TX") (class "Default")
      (node (ref "EC1") (pin "3") (pinfunction "Tx_3") (pintype "passive"))
      (node (ref "J1") (pin "8") (pintype "passive"))
    )
    (net (code "68") (name "/S2_RS232_RX") (class "Default")
      (node (ref "J1") (pin "4") (pintype "passive"))
      (node (ref "R10") (pin "1") (pinfunction "1_1") (pintype "passive"))
    )
    (net (code "69") (name "/S2_RS232_TX") (class "Default")
      (node (ref "J1") (pin "3") (pintype "passive"))
      (node (ref "R4") (pin "1") (pinfunction "1_1") (pintype "passive"))
    )
    (net (code "70") (name "/S2_RX") (class "Default")
      (node (ref "EC2") (pin "5") (pinfunction "Rx_5") (pintype "passive"))
      (node (ref "J1") (pin "5") (pintype "passive"))
    )
    (net (code "71") (name "/S2_TTL_RX") (class "Default")
      (node (ref "Q4") (pin "3") (pinfunction "C_3") (pintype "passive"))
      (node (ref "R8") (pin "2") (pinfunction "2_2") (pintype "passive"))
      (node (ref "U1") (pin "13") (pinfunction "PA3_13") (pintype "bidirectional"))
    )
    (net (code "72") (name "/S2_TTL_TX") (class "Default")
      (node (ref "R2") (pin "2") (pinfunction "2_2") (pintype "passive"))
      (node (ref "U1") (pin "12") (pinfunction "PA2_12") (pintype "bidirectional"))
    )
    (net (code "73") (name "/S2_TX") (class "Default")
      (node (ref "EC2") (pin "3") (pinfunction "Tx_3") (pintype "passive"))
      (node (ref "J1") (pin "6") (pintype "passive"))
    )
    (net (code "74") (name "/SWCLK") (class "Default")
      (node (ref "P1") (pin "3") (pinfunction "3_3") (pintype "passive"))
      (node (ref "U1") (pin "37") (pinfunction "PA14_37") (pintype "bidirectional"))
    )
    (net (code "75") (name "/SWDIO") (class "Default")
      (node (ref "P1") (pin "2") (pinfunction "2_2") (pintype "passive"))
      (node (ref "U1") (pin "34") (pinfunction "PA13_34") (pintype "bidirectional"))
    )
    (net (code "76") (name "/USBDM") (class "Default")
      (node (ref "J2") (pin "2") (pinfunction "D-_2") (pintype "passive"))
      (node (ref "U1") (pin "32") (pinfunction "PA11_32") (pintype "bidirectional"))
    )
    (net (code "77") (name "/USBDP") (class "Default")
      (node (ref "J2") (pin "3") (pinfunction "D+_3") (pintype "passive"))
      (node (ref "R17") (pin "1") (pinfunction "1_1") (pintype "passive"))
      (node (ref "U1") (pin "33") (pinfunction "PA12_33") (pintype "bidirectional"))
    )
    (net (code "78") (name "/pDBIN") (class "Default")
      (node (ref "D28") (pin "1") (pinfunction "A_1") (pintype "passive"))
      (node (ref "EC3") (pin "78") (pinfunction "pDBIN  _78") (pintype "passive"))
      (node (ref "U10") (pin "5") (pinfunction "2B_5") (pintype "input"))
      (node (ref "U6") (pin "2") (pinfunction "1B_2") (pintype "input"))
    )
    (net (code "79") (name "/pDBIN_3v3") (class "Default")
      (node (ref "D27") (pin "2") (pinfunction "K_2") (pintype "passive"))
      (node (ref "U1") (pin "11") (pinfunction "PA1_11") (pintype "bidirectional"))
    )
    (net (code "80") (name "/pWR") (class "Default")
      (node (ref "EC3") (pin "77") (pinfunction "pWR*  _77") (pintype "passive"))
      (node (ref "U1") (pin "38") (pinfunction "PA15_38") (pintype "bidirectional"))
      (node (ref "U8") (pin "1") (pinfunction "1A_1") (pintype "input"))
    )
    (net (code "81") (name "/sINP") (class "Default")
      (node (ref "D26") (pin "1") (pinfunction "A_1") (pintype "passive"))
      (node (ref "EC3") (pin "46") (pinfunction "sINP_46") (pintype "passive"))
      (node (ref "U10") (pin "4") (pinfunction "2A_4") (pintype "input"))
      (node (ref "U6") (pin "1") (pinfunction "1A_1") (pintype "input"))
    )
    (net (code "82") (name "/sINP_3v3") (class "Default")
      (node (ref "D25") (pin "2") (pinfunction "K_2") (pintype "passive"))
      (node (ref "U1") (pin "17") (pinfunction "PA7_17") (pintype "bidirectional"))
    )
    (net (code "83") (name "/sOUT") (class "Default")
      (node (ref "D22") (pin "1") (pinfunction "A_1") (pintype "passive"))
      (node (ref "EC3") (pin "45") (pinfunction "sOUT_45") (pintype "passive"))
      (node (ref "U10") (pin "2") (pinfunction "1B_2") (pintype "input"))
      (node (ref "U6") (pin "4") (pinfunction "2B_4") (pintype "input"))
    )
    (net (code "84") (name "/sOUT_3v3") (class "Default")
      (node (ref "D21") (pin "2") (pinfunction "K_2") (pintype "passive"))
      (node (ref "U1") (pin "16") (pinfunction "PA6_16") (pintype "bidirectional"))
    )
    (net (code "85") (name "GND") (class "Default")
      (node (ref "C1") (pin "2") (pinfunction "2_2") (pintype "passive"))
      (node (ref "C10") (pin "1") (pinfunction "1_1") (pintype "passive"))
      (node (ref "C11") (pin "1") (pinfunction "1_1") (pintype "passive"))
      (node (ref "C12") (pin "1") (pinfunction "1_1") (pintype "passive"))
      (node (ref "C13") (pin "1") (pinfunction "1_1") (pintype "passive"))
      (node (ref "C2") (pin "2") (pinfunction "2_2") (pintype "passive"))
      (node (ref "C3") (pin "1") (pinfunction "1_1") (pintype "passive"))
      (node (ref "C4") (pin "2") (pinfunction "2_2") (pintype "passive"))
      (node (ref "C5") (pin "1") (pinfunction "1_1") (pintype "passive"))
      (node (ref "C6") (pin "1") (pinfunction "1_1") (pintype "passive"))
      (node (ref "C7") (pin "2") (pinfunction "2_2") (pintype "passive"))
      (node (ref "C8") (pin "1") (pinfunction "1_1") (pintype "passive"))
      (node (ref "C9") (pin "1") (pinfunction "1_1") (pintype "passive"))
      (node (ref "D1") (pin "1") (pinfunction "A_1") (pintype "passive"))
      (node (ref "D2") (pin "1") (pinfunction "A_1") (pintype "passive"))
      (node (ref "EC1") (pin "13") (pinfunction "GND_13") (pintype "power_in"))
      (node (ref "EC2") (pin "13") (pinfunction "GND_13") (pintype "power_in"))
      (node (ref "EC3") (pin "100") (pinfunction "GND_100") (pintype "passive"))
      (node (ref "EC3") (pin "50") (pinfunction "GND_50") (pintype "passive"))
      (node (ref "J2") (pin "5") (pinfunction "GND_5") (pintype "passive"))
      (node (ref "LED1") (pin "2") (pinfunction "K_2") (pintype "passive"))
      (node (ref "LED2") (pin "2") (pinfunction "K_2") (pintype "passive"))
      (node (ref "LED3") (pin "1") (pinfunction "A_1") (pintype "passive"))
      (node (ref "P1") (pin "1") (pinfunction "1_1") (pintype "passive"))
      (node (ref "Q3") (pin "1") (pinfunction "E_1") (pintype "passive"))
      (node (ref "Q4") (pin "1") (pinfunction "E_1") (pintype "passive"))
      (node (ref "R15") (pin "1") (pinfunction "1_1") (pintype "passive"))
      (node (ref "SW1") (pin "1") (pintype "passive"))
      (node (ref "U1") (pin "23") (pinfunction "VSS_1_23") (pintype "power_in"))
      (node (ref "U1") (pin "35") (pinfunction "VSS_2_35") (pintype "power_in"))
      (node (ref "U1") (pin "47") (pinfunction "VSS_3_47") (pintype "power_in"))
      (node (ref "U1") (pin "8") (pinfunction "VSSA_8") (pintype "power_in"))
      (node (ref "U10") (pin "7") (pinfunction "GND_7") (pintype "power_in"))
      (node (ref "U2") (pin "8") (pinfunction "GND_8") (pintype "power_in"))
      (node (ref "U3") (pin "1") (pinfunction "IN_1") (pintype "passive"))
      (node (ref "U4") (pin "8") (pinfunction "GND_8") (pintype "power_in"))
      (node (ref "U5") (pin "8") (pinfunction "GND_8") (pintype "power_in"))
      (node (ref "U6") (pin "7") (pinfunction "GND_7") (pintype "power_in"))
      (node (ref "U7") (pin "2") (pinfunction "GND_2") (pintype "passive"))
      (node (ref "U8") (pin "7") (pinfunction "GND_7") (pintype "power_in"))
      (node (ref "U9") (pin "1") (pinfunction "ADJ/GND_1") (pintype "power_in"))
    )
    (net (code "86") (name "Net-(D1-K)") (class "Default")
      (node (ref "D1") (pin "2") (pinfunction "K_2") (pintype "passive"))
      (node (ref "Q3") (pin "2") (pinfunction "B_2") (pintype "passive"))
      (node (ref "R9") (pin "2") (pinfunction "2_2") (pintype "passive"))
    )
    (net (code "87") (name "Net-(D2-K)") (class "Default")
      (node (ref "D2") (pin "2") (pinfunction "K_2") (pintype "passive"))
      (node (ref "Q4") (pin "2") (pinfunction "B_2") (pintype "passive"))
      (node (ref "R10") (pin "2") (pinfunction "2_2") (pintype "passive"))
    )
    (net (code "88") (name "Net-(D3-A)") (class "Default")
      (node (ref "D3") (pin "1") (pinfunction "A_1") (pintype "passive"))
      (node (ref "D4") (pin "2") (pinfunction "K_2") (pintype "passive"))
    )
    (net (code "89") (name "Net-(D5-A)") (class "Default")
      (node (ref "D5") (pin "1") (pinfunction "A_1") (pintype "passive"))
      (node (ref "D6") (pin "2") (pinfunction "K_2") (pintype "passive"))
    )
    (net (code "90") (name "Net-(D7-A)") (class "Default")
      (node (ref "D7") (pin "1") (pinfunction "A_1") (pintype "passive"))
      (node (ref "D8") (pin "2") (pinfunction "K_2") (pintype "passive"))
    )
    (net (code "91") (name "Net-(D10-K)") (class "Default")
      (node (ref "D10") (pin "2") (pinfunction "K_2") (pintype "passive"))
      (node (ref "D9") (pin "1") (pinfunction "A_1") (pintype "passive"))
    )
    (net (code "92") (name "Net-(D11-A)") (class "Default")
      (node (ref "D11") (pin "1") (pinfunction "A_1") (pintype "passive"))
      (node (ref "D12") (pin "2") (pinfunction "K_2") (pintype "passive"))
    )
    (net (code "93") (name "Net-(D13-A)") (class "Default")
      (node (ref "D13") (pin "1") (pinfunction "A_1") (pintype "passive"))
      (node (ref "D14") (pin "2") (pinfunction "K_2") (pintype "passive"))
    )
    (net (code "94") (name "Net-(D15-A)") (class "Default")
      (node (ref "D15") (pin "1") (pinfunction "A_1") (pintype "passive"))
      (node (ref "D16") (pin "2") (pinfunction "K_2") (pintype "passive"))
    )
    (net (code "95") (name "Net-(D17-A)") (class "Default")
      (node (ref "D17") (pin "1") (pinfunction "A_1") (pintype "passive"))
      (node (ref "D18") (pin "2") (pinfunction "K_2") (pintype "passive"))
    )
    (net (code "96") (name "Net-(D19-A)") (class "Default")
      (node (ref "D19") (pin "1") (pinfunction "A_1") (pintype "passive"))
      (node (ref "D20") (pin "2") (pinfunction "K_2") (pintype "passive"))
    )
    (net (code "97") (name "Net-(D21-A)") (class "Default")
      (node (ref "D21") (pin "1") (pinfunction "A_1") (pintype "passive"))
      (node (ref "D22") (pin "2") (pinfunction "K_2") (pintype "passive"))
    )
    (net (code "98") (name "Net-(D23-A)") (class "Default")
      (node (ref "D23") (pin "1") (pinfunction "A_1") (pintype "passive"))
      (node (ref "D24") (pin "2") (pinfunction "K_2") (pintype "passive"))
    )
    (net (code "99") (name "Net-(D25-A)") (class "Default")
      (node (ref "D25") (pin "1") (pinfunction "A_1") (pintype "passive"))
      (node (ref "D26") (pin "2") (pinfunction "K_2") (pintype "passive"))
    )
    (net (code "100") (name "Net-(D27-A)") (class "Default")
      (node (ref "D27") (pin "1") (pinfunction "A_1") (pintype "passive"))
      (node (ref "D28") (pin "2") (pinfunction "K_2") (pintype "passive"))
    )
    (net (code "101") (name "Net-(D29-A)") (class "Default")
      (node (ref "D29") (pin "1") (pinfunction "A_1") (pintype "passive"))
      (node (ref "P1") (pin "4") (pinfunction "4_4") (pintype "passive"))
    )
    (net (code "102") (name "Net-(D30-A)") (class "Default")
      (node (ref "D30") (pin "1") (pinfunction "A_1") (pintype "passive"))
      (node (ref "J2") (pin "1") (pinfunction "VBUS_1") (pintype "passive"))
    )
    (net (code "103") (name "Net-(LED1-A)") (class "Default")
      (node (ref "LED1") (pin "1") (pinfunction "A_1") (pintype "passive"))
      (node (ref "R11") (pin "1") (pinfunction "1_1") (pintype "passive"))
    )
    (net (code "104") (name "Net-(LED2-A)") (class "Default")
      (node (ref "LED2") (pin "1") (pinfunction "A_1") (pintype "passive"))
      (node (ref "R12") (pin "1") (pinfunction "1_1") (pintype "passive"))
    )
    (net (code "105") (name "Net-(LED3-K)") (class "Default")
      (node (ref "LED3") (pin "2") (pinfunction "K_2") (pintype "passive"))
      (node (ref "R13") (pin "1") (pinfunction "1_1") (pintype "passive"))
    )
    (net (code "106") (name "Net-(Q1-B)") (class "Default")
      (node (ref "Q1") (pin "2") (pinfunction "B_2") (pintype "passive"))
      (node (ref "R1") (pin "1") (pinfunction "1_1") (pintype "passive"))
    )
    (net (code "107") (name "Net-(Q1-C)") (class "Default")
      (node (ref "Q1") (pin "3") (pinfunction "C_3") (pintype "passive"))
      (node (ref "R3") (pin "2") (pinfunction "2_2") (pintype "passive"))
      (node (ref "R5") (pin "2") (pinfunction "2_2") (pintype "passive"))
    )
    (net (code "108") (name "Net-(Q2-B)") (class "Default")
      (node (ref "Q2") (pin "2") (pinfunction "B_2") (pintype "passive"))
      (node (ref "R2") (pin "1") (pinfunction "1_1") (pintype "passive"))
    )
    (net (code "109") (name "Net-(Q2-C)") (class "Default")
      (node (ref "Q2") (pin "3") (pinfunction "C_3") (pintype "passive"))
      (node (ref "R4") (pin "2") (pinfunction "2_2") (pintype "passive"))
      (node (ref "R6") (pin "2") (pinfunction "2_2") (pintype "passive"))
    )
    (net (code "110") (name "Net-(U1A-BOOT0)") (class "Default")
      (node (ref "R15") (pin "2") (pinfunction "2_2") (pintype "passive"))
      (node (ref "U1") (pin "44") (pinfunction "BOOT0_44") (pintype "input"))
    )
    (net (code "111") (name "Net-(U1A-NRST)") (class "Default")
      (node (ref "R16") (pin "1") (pinfunction "1_1") (pintype "passive"))
      (node (ref "SW1") (pin "2") (pinfunction "2_2") (pintype "passive"))
      (node (ref "U1") (pin "7") (pinfunction "NRST_7") (pintype "bidirectional"))
    )
    (net (code "112") (name "Net-(U1A-PD0-OSC_IN)") (class "Default")
      (node (ref "C8") (pin "2") (pinfunction "2_2") (pintype "passive"))
      (node (ref "U1") (pin "5") (pinfunction "PD0-OSC_IN_5") (pintype "bidirectional"))
      (node (ref "Y1") (pin "2") (pinfunction "2_2") (pintype "passive"))
    )
    (net (code "113") (name "Net-(U1A-PD1-OSC_OUT)") (class "Default")
      (node (ref "C9") (pin "2") (pinfunction "2_2") (pintype "passive"))
      (node (ref "U1") (pin "6") (pinfunction "PD1-OSC_OUT_6") (pintype "bidirectional"))
      (node (ref "Y1") (pin "1") (pinfunction "1_1") (pintype "passive"))
    )
    (net (code "114") (name "Net-(U10A-1A)") (class "Default")
      (node (ref "U10") (pin "1") (pinfunction "1A_1") (pintype "input"))
      (node (ref "U6") (pin "3") (pinfunction "2A_3") (pintype "input"))
      (node (ref "U8") (pin "2") (pinfunction "~{1Y}_2") (pintype "output"))
    )
    (net (code "115") (name "unconnected-(EC1-(TTL)DSR-Pad6)") (class "Default")
      (node (ref "EC1") (pin "6") (pinfunction "(TTL)DSR_6") (pintype "passive+no_connect"))
    )
    (net (code "116") (name "unconnected-(EC1-(TTL)DTR-Pad2)") (class "Default")
      (node (ref "EC1") (pin "2") (pinfunction "(TTL)DTR_2") (pintype "passive+no_connect"))
    )
    (net (code "117") (name "unconnected-(EC1-(TTL)Rx-Pad12)") (class "Default")
      (node (ref "EC1") (pin "12") (pinfunction "(TTL)Rx_12") (pintype "passive+no_connect"))
    )
    (net (code "118") (name "unconnected-(EC1-(TTL)Tx-Pad10)") (class "Default")
      (node (ref "EC1") (pin "10") (pinfunction "(TTL)Tx_10") (pintype "passive+no_connect"))
    )
    (net (code "119") (name "unconnected-(EC1-CTS-Pad9)") (class "Default")
      (node (ref "EC1") (pin "9") (pinfunction "CTS_9") (pintype "passive+no_connect"))
    )
    (net (code "120") (name "unconnected-(EC1-DCD-Pad15)") (class "Default")
      (node (ref "EC1") (pin "15") (pinfunction "DCD_15") (pintype "passive+no_connect"))
    )
    (net (code "121") (name "unconnected-(EC1-DSR-Pad11)") (class "Default")
      (node (ref "EC1") (pin "11") (pinfunction "DSR_11") (pintype "passive+no_connect"))
    )
    (net (code "122") (name "unconnected-(EC1-DTR-Pad14)") (class "Default")
      (node (ref "EC1") (pin "14") (pinfunction "DTR_14") (pintype "passive+no_connect"))
    )
    (net (code "123") (name "unconnected-(EC1-PGND-Pad1)") (class "Default")
      (node (ref "EC1") (pin "1") (pinfunction "PGND_1") (pintype "passive+no_connect"))
    )
    (net (code "124") (name "unconnected-(EC1-RTS-Pad7)") (class "Default")
      (node (ref "EC1") (pin "7") (pinfunction "RTS_7") (pintype "passive+no_connect"))
    )
    (net (code "125") (name "unconnected-(EC2-(TTL)DSR-Pad6)") (class "Default")
      (node (ref "EC2") (pin "6") (pinfunction "(TTL)DSR_6") (pintype "passive+no_connect"))
    )
    (net (code "126") (name "unconnected-(EC2-(TTL)DTR-Pad2)") (class "Default")
      (node (ref "EC2") (pin "2") (pinfunction "(TTL)DTR_2") (pintype "passive+no_connect"))
    )
    (net (code "127") (name "unconnected-(EC2-(TTL)Rx-Pad12)") (class "Default")
      (node (ref "EC2") (pin "12") (pinfunction "(TTL)Rx_12") (pintype "passive+no_connect"))
    )
    (net (code "128") (name "unconnected-(EC2-(TTL)Tx-Pad10)") (class "Default")
      (node (ref "EC2") (pin "10") (pinfunction "(TTL)Tx_10") (pintype "passive+no_connect"))
    )
    (net (code "129") (name "unconnected-(EC2-CTS-Pad9)") (class "Default")
      (node (ref "EC2") (pin "9") (pinfunction "CTS_9") (pintype "passive+no_connect"))
    )
    (net (code "130") (name "unconnected-(EC2-DCD-Pad15)") (class "Default")
      (node (ref "EC2") (pin "15") (pinfunction "DCD_15") (pintype "passive+no_connect"))
    )
    (net (code "131") (name "unconnected-(EC2-DSR-Pad11)") (class "Default")
      (node (ref "EC2") (pin "11") (pinfunction "DSR_11") (pintype "passive+no_connect"))
    )
    (net (code "132") (name "unconnected-(EC2-DTR-Pad14)") (class "Default")
      (node (ref "EC2") (pin "14") (pinfunction "DTR_14") (pintype "passive+no_connect"))
    )
    (net (code "133") (name "unconnected-(EC2-PGND-Pad1)") (class "Default")
      (node (ref "EC2") (pin "1") (pinfunction "PGND_1") (pintype "passive+no_connect"))
    )
    (net (code "134") (name "unconnected-(EC2-RTS-Pad7)") (class "Default")
      (node (ref "EC2") (pin "7") (pinfunction "RTS_7") (pintype "passive+no_connect"))
    )
    (net (code "135") (name "unconnected-(EC3-A16  -Pad16)") (class "Default")
      (node (ref "EC3") (pin "16") (pinfunction "A16  _16") (pintype "passive"))
    )
    (net (code "136") (name "unconnected-(EC3-A17-Pad17)") (class "Default")
      (node (ref "EC3") (pin "17") (pinfunction "A17_17") (pintype "passive"))
    )
    (net (code "137") (name "unconnected-(EC3-A18 -Pad15)") (class "Default")
      (node (ref "EC3") (pin "15") (pinfunction "A18 _15") (pintype "passive"))
    )
    (net (code "138") (name "unconnected-(EC3-A19-Pad59)") (class "Default")
      (node (ref "EC3") (pin "59") (pinfunction "A19_59") (pintype "passive"))
    )
    (net (code "139") (name "unconnected-(EC3-A20-Pad61)") (class "Default")
      (node (ref "EC3") (pin "61") (pinfunction "A20_61") (pintype "passive"))
    )
    (net (code "140") (name "unconnected-(EC3-A21-Pad62)") (class "Default")
      (node (ref "EC3") (pin "62") (pinfunction "A21_62") (pintype "passive"))
    )
    (net (code "141") (name "unconnected-(EC3-A22-Pad63)") (class "Default")
      (node (ref "EC3") (pin "63") (pinfunction "A22_63") (pintype "passive"))
    )
    (net (code "142") (name "unconnected-(EC3-A23-Pad64)") (class "Default")
      (node (ref "EC3") (pin "64") (pinfunction "A23_64") (pintype "passive"))
    )
    (net (code "143") (name "unconnected-(EC3-ADSB*-Pad22)") (class "Default")
      (node (ref "EC3") (pin "22") (pinfunction "ADSB*_22") (pintype "passive"))
    )
    (net (code "144") (name "unconnected-(EC3-CDSB*-Pad19)") (class "Default")
      (node (ref "EC3") (pin "19") (pinfunction "CDSB*_19") (pintype "passive"))
    )
    (net (code "145") (name "unconnected-(EC3-CLOCK -Pad49)") (class "Default")
      (node (ref "EC3") (pin "49") (pinfunction "CLOCK _49") (pintype "passive"))
    )
    (net (code "146") (name "unconnected-(EC3-DMA_0*-Pad55)") (class "Default")
      (node (ref "EC3") (pin "55") (pinfunction "DMA_0*_55") (pintype "passive"))
    )
    (net (code "147") (name "unconnected-(EC3-DMA_1*-Pad56)") (class "Default")
      (node (ref "EC3") (pin "56") (pinfunction "DMA_1*_56") (pintype "passive"))
    )
    (net (code "148") (name "unconnected-(EC3-DMA_2*-Pad57)") (class "Default")
      (node (ref "EC3") (pin "57") (pinfunction "DMA_2*_57") (pintype "passive"))
    )
    (net (code "149") (name "unconnected-(EC3-DMA_3*-Pad14)") (class "Default")
      (node (ref "EC3") (pin "14") (pinfunction "DMA_3*_14") (pintype "passive"))
    )
    (net (code "150") (name "unconnected-(EC3-DODSB*-Pad23)") (class "Default")
      (node (ref "EC3") (pin "23") (pinfunction "DODSB*_23") (pintype "passive"))
    )
    (net (code "151") (name "unconnected-(EC3-ERROR*-Pad98)") (class "Default")
      (node (ref "EC3") (pin "98") (pinfunction "ERROR*_98") (pintype "passive"))
    )
    (net (code "152") (name "unconnected-(EC3-HOLD* -Pad74)") (class "Default")
      (node (ref "EC3") (pin "74") (pinfunction "HOLD* _74") (pintype "passive"))
    )
    (net (code "153") (name "unconnected-(EC3-INT*-Pad73)") (class "Default")
      (node (ref "EC3") (pin "73") (pinfunction "INT*_73") (pintype "passive"))
    )
    (net (code "154") (name "unconnected-(EC3-MWRT-Pad68)") (class "Default")
      (node (ref "EC3") (pin "68") (pinfunction "MWRT_68") (pintype "passive"))
    )
    (net (code "155") (name "unconnected-(EC3-NDEF-Pad21)") (class "Default")
      (node (ref "EC3") (pin "21") (pinfunction "NDEF_21") (pintype "passive"))
    )
    (net (code "156") (name "unconnected-(EC3-NDEF-Pad65)") (class "Default")
      (node (ref "EC3") (pin "65") (pinfunction "NDEF_65") (pintype "passive"))
    )
    (net (code "157") (name "unconnected-(EC3-NDEF-Pad66)") (class "Default")
      (node (ref "EC3") (pin "66") (pinfunction "NDEF_66") (pintype "passive"))
    )
    (net (code "158") (name "unconnected-(EC3-NMI*-Pad12)") (class "Default")
      (node (ref "EC3") (pin "12") (pinfunction "NMI*_12") (pintype "passive"))
    )
    (net (code "159") (name "unconnected-(EC3-PHANTOM*-Pad67)") (class "Default")
      (node (ref "EC3") (pin "67") (pinfunction "PHANTOM*_67") (pintype "passive"))
    )
    (net (code "160") (name "unconnected-(EC3-PHI-Pad24)") (class "Default")
      (node (ref "EC3") (pin "24") (pinfunction "PHI_24") (pintype "passive"))
    )
    (net (code "161") (name "unconnected-(EC3-POC*-Pad99)") (class "Default")
      (node (ref "EC3") (pin "99") (pinfunction "POC*_99") (pintype "passive"))
    )
    (net (code "162") (name "unconnected-(EC3-PS-Pad70)") (class "Default")
      (node (ref "EC3") (pin "70") (pinfunction "PS_70") (pintype "passive"))
    )
    (net (code "163") (name "unconnected-(EC3-PWRFAIL*-Pad13)") (class "Default")
      (node (ref "EC3") (pin "13") (pinfunction "PWRFAIL*_13") (pintype "passive"))
    )
    (net (code "164") (name "unconnected-(EC3-RDY-Pad72)") (class "Default")
      (node (ref "EC3") (pin "72") (pinfunction "RDY_72") (pintype "passive"))
    )
    (net (code "165") (name "unconnected-(EC3-RESET*-Pad75)") (class "Default")
      (node (ref "EC3") (pin "75") (pinfunction "RESET*_75") (pintype "passive"))
    )
    (net (code "166") (name "unconnected-(EC3-RFU-Pad27)") (class "Default")
      (node (ref "EC3") (pin "27") (pinfunction "RFU_27") (pintype "passive"))
    )
    (net (code "167") (name "unconnected-(EC3-RFU-Pad28)") (class "Default")
      (node (ref "EC3") (pin "28") (pinfunction "RFU_28") (pintype "passive"))
    )
    (net (code "168") (name "unconnected-(EC3-RFU-Pad69)") (class "Default")
      (node (ref "EC3") (pin "69") (pinfunction "RFU_69") (pintype "passive"))
    )
    (net (code "169") (name "unconnected-(EC3-RFU-Pad71)") (class "Default")
      (node (ref "EC3") (pin "71") (pinfunction "RFU_71") (pintype "passive"))
    )
    (net (code "170") (name "unconnected-(EC3-SDSB*-Pad18)") (class "Default")
      (node (ref "EC3") (pin "18") (pinfunction "SDSB*_18") (pintype "passive"))
    )
    (net (code "171") (name "unconnected-(EC3-SIXTN*-Pad60)") (class "Default")
      (node (ref "EC3") (pin "60") (pinfunction "SIXTN*_60") (pintype "passive"))
    )
    (net (code "172") (name "unconnected-(EC3-SLAVE_CLR*-Pad54)") (class "Default")
      (node (ref "EC3") (pin "54") (pinfunction "SLAVE_CLR*_54") (pintype "passive"))
    )
    (net (code "173") (name "unconnected-(EC3-SnsDSB-Pad53)") (class "Default")
      (node (ref "EC3") (pin "53") (pinfunction "SnsDSB_53") (pintype "passive"))
    )
    (net (code "174") (name "unconnected-(EC3-VI0-Pad4)") (class "Default")
      (node (ref "EC3") (pin "4") (pinfunction "VI0_4") (pintype "passive"))
    )
    (net (code "175") (name "unconnected-(EC3-VI1-Pad5)") (class "Default")
      (node (ref "EC3") (pin "5") (pinfunction "VI1_5") (pintype "passive"))
    )
    (net (code "176") (name "unconnected-(EC3-VI2-Pad6)") (class "Default")
      (node (ref "EC3") (pin "6") (pinfunction "VI2_6") (pintype "passive"))
    )
    (net (code "177") (name "unconnected-(EC3-VI3-Pad7)") (class "Default")
      (node (ref "EC3") (pin "7") (pinfunction "VI3_7") (pintype "passive"))
    )
    (net (code "178") (name "unconnected-(EC3-VI4-Pad8)") (class "Default")
      (node (ref "EC3") (pin "8") (pinfunction "VI4_8") (pintype "passive"))
    )
    (net (code "179") (name "unconnected-(EC3-VI5-Pad9)") (class "Default")
      (node (ref "EC3") (pin "9") (pinfunction "VI5_9") (pintype "passive"))
    )
    (net (code "180") (name "unconnected-(EC3-VI6-Pad10)") (class "Default")
      (node (ref "EC3") (pin "10") (pinfunction "VI6_10") (pintype "passive"))
    )
    (net (code "181") (name "unconnected-(EC3-VI7-Pad11)") (class "Default")
      (node (ref "EC3") (pin "11") (pinfunction "VI7_11") (pintype "passive"))
    )
    (net (code "182") (name "unconnected-(EC3-XRDY-Pad3)") (class "Default")
      (node (ref "EC3") (pin "3") (pinfunction "XRDY_3") (pintype "passive"))
    )
    (net (code "183") (name "unconnected-(EC3-pHLDA-Pad26)") (class "Default")
      (node (ref "EC3") (pin "26") (pinfunction "pHLDA_26") (pintype "passive"))
    )
    (net (code "184") (name "unconnected-(EC3-pSTVAL*-Pad25)") (class "Default")
      (node (ref "EC3") (pin "25") (pinfunction "pSTVAL*_25") (pintype "passive"))
    )
    (net (code "185") (name "unconnected-(EC3-pSYNC-Pad76)") (class "Default")
      (node (ref "EC3") (pin "76") (pinfunction "pSYNC_76") (pintype "passive"))
    )
    (net (code "186") (name "unconnected-(EC3-sHLTA-Pad48)") (class "Default")
      (node (ref "EC3") (pin "48") (pinfunction "sHLTA_48") (pintype "passive"))
    )
    (net (code "187") (name "unconnected-(EC3-sINTA-Pad96)") (class "Default")
      (node (ref "EC3") (pin "96") (pinfunction "sINTA_96") (pintype "passive"))
    )
    (net (code "188") (name "unconnected-(EC3-sM1-Pad44)") (class "Default")
      (node (ref "EC3") (pin "44") (pinfunction "sM1_44") (pintype "passive"))
    )
    (net (code "189") (name "unconnected-(EC3-sMEMR-Pad47)") (class "Default")
      (node (ref "EC3") (pin "47") (pinfunction "sMEMR_47") (pintype "passive"))
    )
    (net (code "190") (name "unconnected-(EC3-sWO*-Pad97)") (class "Default")
      (node (ref "EC3") (pin "97") (pinfunction "sWO*_97") (pintype "passive"))
    )
    (net (code "191") (name "unconnected-(EC3-sXTRQ*-Pad58)") (class "Default")
      (node (ref "EC3") (pin "58") (pinfunction "sXTRQ*_58") (pintype "passive"))
    )
    (net (code "192") (name "unconnected-(EC3-wINHB-Pad20)") (class "Default")
      (node (ref "EC3") (pin "20") (pinfunction "wINHB_20") (pintype "passive"))
    )
    (net (code "193") (name "unconnected-(J2-ID-Pad4)") (class "Default")
      (node (ref "J2") (pin "4") (pinfunction "ID_4") (pintype "passive"))
    )
    (net (code "194") (name "unconnected-(J2-SHIELD-Pad6)") (class "Default")
      (node (ref "J2") (pin "6") (pinfunction "SHIELD_6") (pintype "passive"))
    )
    (net (code "195") (name "unconnected-(U1A-PA0-WKUP-Pad10)") (class "Default")
      (node (ref "U1") (pin "10") (pinfunction "PA0-WKUP_10") (pintype "bidirectional"))
    )
    (net (code "196") (name "unconnected-(U1A-PC13-TAMPER-RTC-Pad2)") (class "Default")
      (node (ref "U1") (pin "2") (pinfunction "PC13-TAMPER-RTC_2") (pintype "bidirectional"))
    )
    (net (code "197") (name "unconnected-(U1A-PC14-OSC32_IN-Pad3)") (class "Default")
      (node (ref "U1") (pin "3") (pinfunction "PC14-OSC32_IN_3") (pintype "bidirectional"))
    )
    (net (code "198") (name "unconnected-(U1A-PC15-OSC32_OUT-Pad4)") (class "Default")
      (node (ref "U1") (pin "4") (pinfunction "PC15-OSC32_OUT_4") (pintype "bidirectional"))
    )
    (net (code "199") (name "unconnected-(U1B-VBAT-Pad1)") (class "Default")
      (node (ref "U1") (pin "1") (pinfunction "VBAT_1") (pintype "power_in"))
    )
    (net (code "200") (name "unconnected-(U5-A5-Pad12)") (class "Default")
      (node (ref "U5") (pin "12") (pinfunction "A5_12") (pintype "input"))
    )
    (net (code "201") (name "unconnected-(U5-A6-Pad14)") (class "Default")
      (node (ref "U5") (pin "14") (pinfunction "A6_14") (pintype "input"))
    )
    (net (code "202") (name "unconnected-(U5-G2-Pad15)") (class "Default")
      (node (ref "U5") (pin "15") (pinfunction "G2_15") (pintype "input"))
    )
    (net (code "203") (name "unconnected-(U5-Y5-Pad11)") (class "Default")
      (node (ref "U5") (pin "11") (pinfunction "Y5_11") (pintype "output"))
    )
    (net (code "204") (name "unconnected-(U5-Y6-Pad13)") (class "Default")
      (node (ref "U5") (pin "13") (pinfunction "Y6_13") (pintype "output"))
    )
  )
)
